# 9v_to_5v.net
KiCad netlist of a schematic drawn in Altium Designer
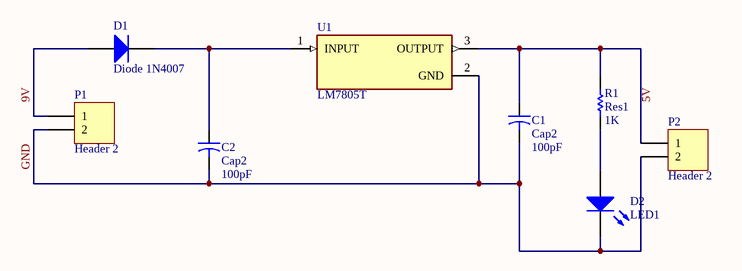
[diagram p0: 9v to 5v.SchDoc]

(export (version "E")
  (design (tool "Eeschema 10.0.6"))
  (components
    (comp (ref "C1")
      (value "Cap2")
      (footprint "CAPR5-4X5")
      (description "Capacitor")
      (fields (field (name "ALTIUM_VALUE") "100pF") (field (name "PUBLISHER") "Altium Limited"))
      (libsource (lib "Miscellaneous Devices") (part "Cap2"))
    )
    (comp (ref "C2")
      (value "Cap2")
      (footprint "CAPR5-4X5")
      (description "Capacitor")
      (fields (field (name "ALTIUM_VALUE") "100pF") (field (name "PUBLISHER") "Altium Limited"))
      (libsource (lib "Miscellaneous Devices") (part "Cap2"))
    )
    (comp (ref "D1")
      (value "Diode 1N4007")
      (footprint "DO-41")
      (description "1 Amp General Purpose Rectifier")
      (fields (field (name "PUBLISHER") "Altium Limited"))
      (libsource (lib "Miscellaneous Devices") (part "Diode 1N4007"))
    )
    (comp (ref "D2")
      (value "LED1")
      (footprint "LED-1")
      (description "Typical RED GaAs LED")
      (fields (field (name "PUBLISHER") "Altium Limited"))
      (libsource (lib "Miscellaneous Devices") (part "LED1"))
    )
    (comp (ref "P1")
      (value "Header 2")
      (footprint "HDR1X2")
      (description "Header, 2-Pin")
      (fields (field (name "PUBLISHER") "Altium Limited"))
      (libsource (lib "Miscellaneous Connectors") (part "Header 2"))
    )
    (comp (ref "P2")
      (value "Header 2")
      (footprint "HDR1X2")
      (description "Header, 2-Pin")
      (fields (field (name "PUBLISHER") "Altium Limited"))
      (libsource (lib "Miscellaneous Connectors") (part "Header 2"))
    )
    (comp (ref "R1")
      (value "Res1")
      (footprint "AXIAL-0.3")
      (description "Resistor")
      (fields (field (name "ALTIUM_VALUE") "1K") (field (name "PUBLISHER") "Altium Limited"))
      (libsource (lib "Miscellaneous Devices") (part "Res1"))
    )
    (comp (ref "U1")
      (value "LM7805T")
      (footprint "TO254P1011X457X1950-3")
      (description "3-Terminal 1.5A Positive Fixed Voltage Regulator")
      (fields (field (name "MF") "TAEJIN"))
      (libsource (lib "LM7805T") (part "LM7805T"))
    )
  )
  (nets
    (net (code "2") (name "/9V") (class "Default")
      (node (ref "D1") (pin "1") (pinfunction "A_1") (pintype "passive"))
      (node (ref "P1") (pin "1") (pinfunction "1_1") (pintype "passive"))
    )
    (net (code "3") (name "/GND") (class "Default")
      (node (ref "C1") (pin "2") (pinfunction "2_2") (pintype "passive"))
      (node (ref "C2") (pin "2") (pinfunction "2_2") (pintype "passive"))
      (node (ref "D2") (pin "2") (pinfunction "K_2") (pintype "passive"))
      (node (ref "P1") (pin "2") (pinfunction "2_2") (pintype "passive"))
      (node (ref "P2") (pin "2") (pinfunction "2_2") (pintype "passive"))
      (node (ref "U1") (pin "2") (pinfunction "GND_2") (pintype "power_in"))
    )
    (net (code "4") (name "Net-(D1-K)") (class "Default")
      (node (ref "C2") (pin "1") (pinfunction "1_1") (pintype "passive"))
      (node (ref "D1") (pin "2") (pinfunction "K_2") (pintype "passive"))
      (node (ref "U1") (pin "1") (pinfunction "INPUT_1") (pintype "input"))
    )
    (net (code "5") (name "Net-(D2-A)") (class "Default")
      (node (ref "D2") (pin "1") (pinfunction "A_1") (pintype "passive"))
      (node (ref "R1") (pin "1") (pinfunction "1_1") (pintype "passive"))
    )
    (net (code "6") (name "Net-(U1-OUTPUT)") (class "Default")
      (node (ref "C1") (pin "1") (pinfunction "1_1") (pintype "passive"))
      (node (ref "P2") (pin "1") (pinfunction "1_1") (pintype "passive"))
      (node (ref "R1") (pin "2") (pinfunction "2_2") (pintype "passive"))
      (node (ref "U1") (pin "3") (pinfunction "OUTPUT_3") (pintype "output"))
    )
  )
)
